# sstate_relay_discharge.net
KiCad netlist of a schematic drawn in Altium Designer
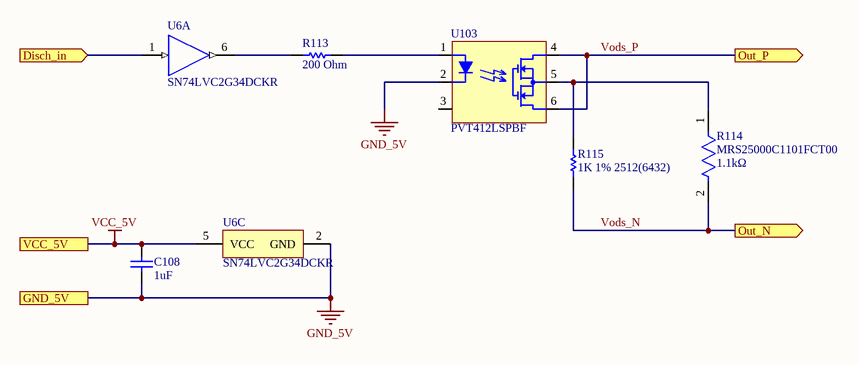
[diagram p0: sstate_relay_discharge.SchDoc]

(export (version "E")
  (design (tool "Eeschema 10.0.6"))
  (components
    (comp (ref "C108")
      (value "1uF")
      (footprint "CAPC0603(1608)100_N")
      (description "CAP 1uF 50V ±20% 0603 (1608 Metric) Thickness 1mm SMD")
      (fields (field (name "TOLERANCE") "Â±20%") (field (name "Comment") "CAP 1uF 50V 0603(1608)"))
      (libsource (lib "Altium Content Vault") (part "CAP"))
    )
    (comp (ref "R113")
      (value "200 Ohm")
      (footprint "RESC2013X60X40NL20T25")
      (fields (field (name "MANUFACTURER") "Panasonic") (field (name "PART NUMBER") "ERA6AEB201V"))
      (libsource (lib "Altium Content Vault") (part "RES"))
    )
    (comp (ref "R114")
      (value "MRS25000C1101FCT00")
      (footprint "FP-MRS25-MFG")
      (description "RES 1.1K OHM 0.6W 1% AXIAL")
      (fields
        (field (name "MANUFACTURER") "Vishay BC Components")
        (field (name "OCTOPART") "https://octopart.com/mrs25000c1101fct00-vishay-43740214")
        (field (name "ALTIUM_VALUE") "1.1kΩ")
      )
      (libsource (lib "Altium Content Vault") (part "1029c3af85768c4190bb7ad29bc67b5"))
    )
    (comp (ref "R115")
      (value "1K 1% 2512(6432)")
      (footprint "RESC2512(6432)_M")
      (description "1K 1W 1% 2512 (6432 Metric)  SMD")
      (fields (field (name "TOLERANCE") "1 %") (field (name "POWER") "1 W"))
      (libsource (lib "Altium Content Vault") (part "RES"))
    )
    (comp (ref "U6")
      (value "SN74LVC2G34DCKR")
      (footprint "DCK0006A_L")
      (description "Dual Buffer Gate, DCK0006A, LARGE T&R")
      (fields
        (field (name "MANUFACTURER") "Texas Instruments")
        (field (name "GENERIC PART NUMBER") "SN74LVC2G34")
      )
      (libsource (lib "Altium Content Vault") (part "TI-SN74XXX2GXXX-6_A"))
    )
    (comp (ref "U103")
      (value "PVT412LSPBF")
      (footprint "SOP254P980X318-6M-PVT412LSPBF")
      (description "IC RELAY PHOTOVO 400V 120MA 6SMD")
      (fields (field (name "MANUFACTURER") "International Rectifier"))
      (libsource (lib "Altium_Library_POWERLAB") (part "PVT412LSPBF"))
    )
  )
  (nets
    (net (code "1") (name "/Disch_in") (class "Default")
      (node (ref "U6") (pin "1") (pinfunction "1A_1") (pintype "input"))
    )
    (net (code "2") (name "/Vods_N") (class "Default")
      (node (ref "R114") (pin "2") (pinfunction "2_2") (pintype "passive"))
      (node (ref "R115") (pin "1") (pinfunction "1_1") (pintype "passive"))
    )
    (net (code "3") (name "/Vods_P") (class "Default")
      (node (ref "U103") (pin "4") (pinfunction "4_4") (pintype "passive"))
      (node (ref "U103") (pin "6") (pinfunction "6_6") (pintype "passive"))
    )
    (net (code "4") (name "GND_5V") (class "Default")
      (node (ref "C108") (pin "1") (pinfunction "1_1") (pintype "passive"))
      (node (ref "U103") (pin "2") (pinfunction "2_2") (pintype "passive"))
      (node (ref "U6") (pin "2") (pinfunction "GND_2") (pintype "power_in"))
    )
    (net (code "5") (name "Net-(R113-Pad2)") (class "Default")
      (node (ref "R113") (pin "2") (pinfunction "2_2") (pintype "passive"))
      (node (ref "U103") (pin "1") (pinfunction "1_1") (pintype "passive"))
    )
    (net (code "6") (name "Net-(R114-Pad1)") (class "Default")
      (node (ref "R114") (pin "1") (pinfunction "1_1") (pintype "passive"))
      (node (ref "R115") (pin "2") (pinfunction "2_2") (pintype "passive"))
      (node (ref "U103") (pin "5") (pinfunction "5_5") (pintype "passive"))
    )
    (net (code "7") (name "Net-(U6A-1Y)") (class "Default")
      (node (ref "R113") (pin "1") (pinfunction "1_1") (pintype "passive"))
      (node (ref "U6") (pin "6") (pinfunction "1Y_6") (pintype "output"))
    )
    (net (code "8") (name "VCC_5V") (class "Default")
      (node (ref "C108") (pin "2") (pinfunction "2_2") (pintype "passive"))
      (node (ref "U6") (pin "5") (pinfunction "VCC_5") (pintype "power_in"))
    )
    (net (code "9") (name "unconnected-(U103-Pad3)") (class "Default")
      (node (ref "U103") (pin "3") (pinfunction "3_3") (pintype "passive"))
    )
  )
)
